# 4x4.net
KiCad netlist of a schematic drawn in EAGLE
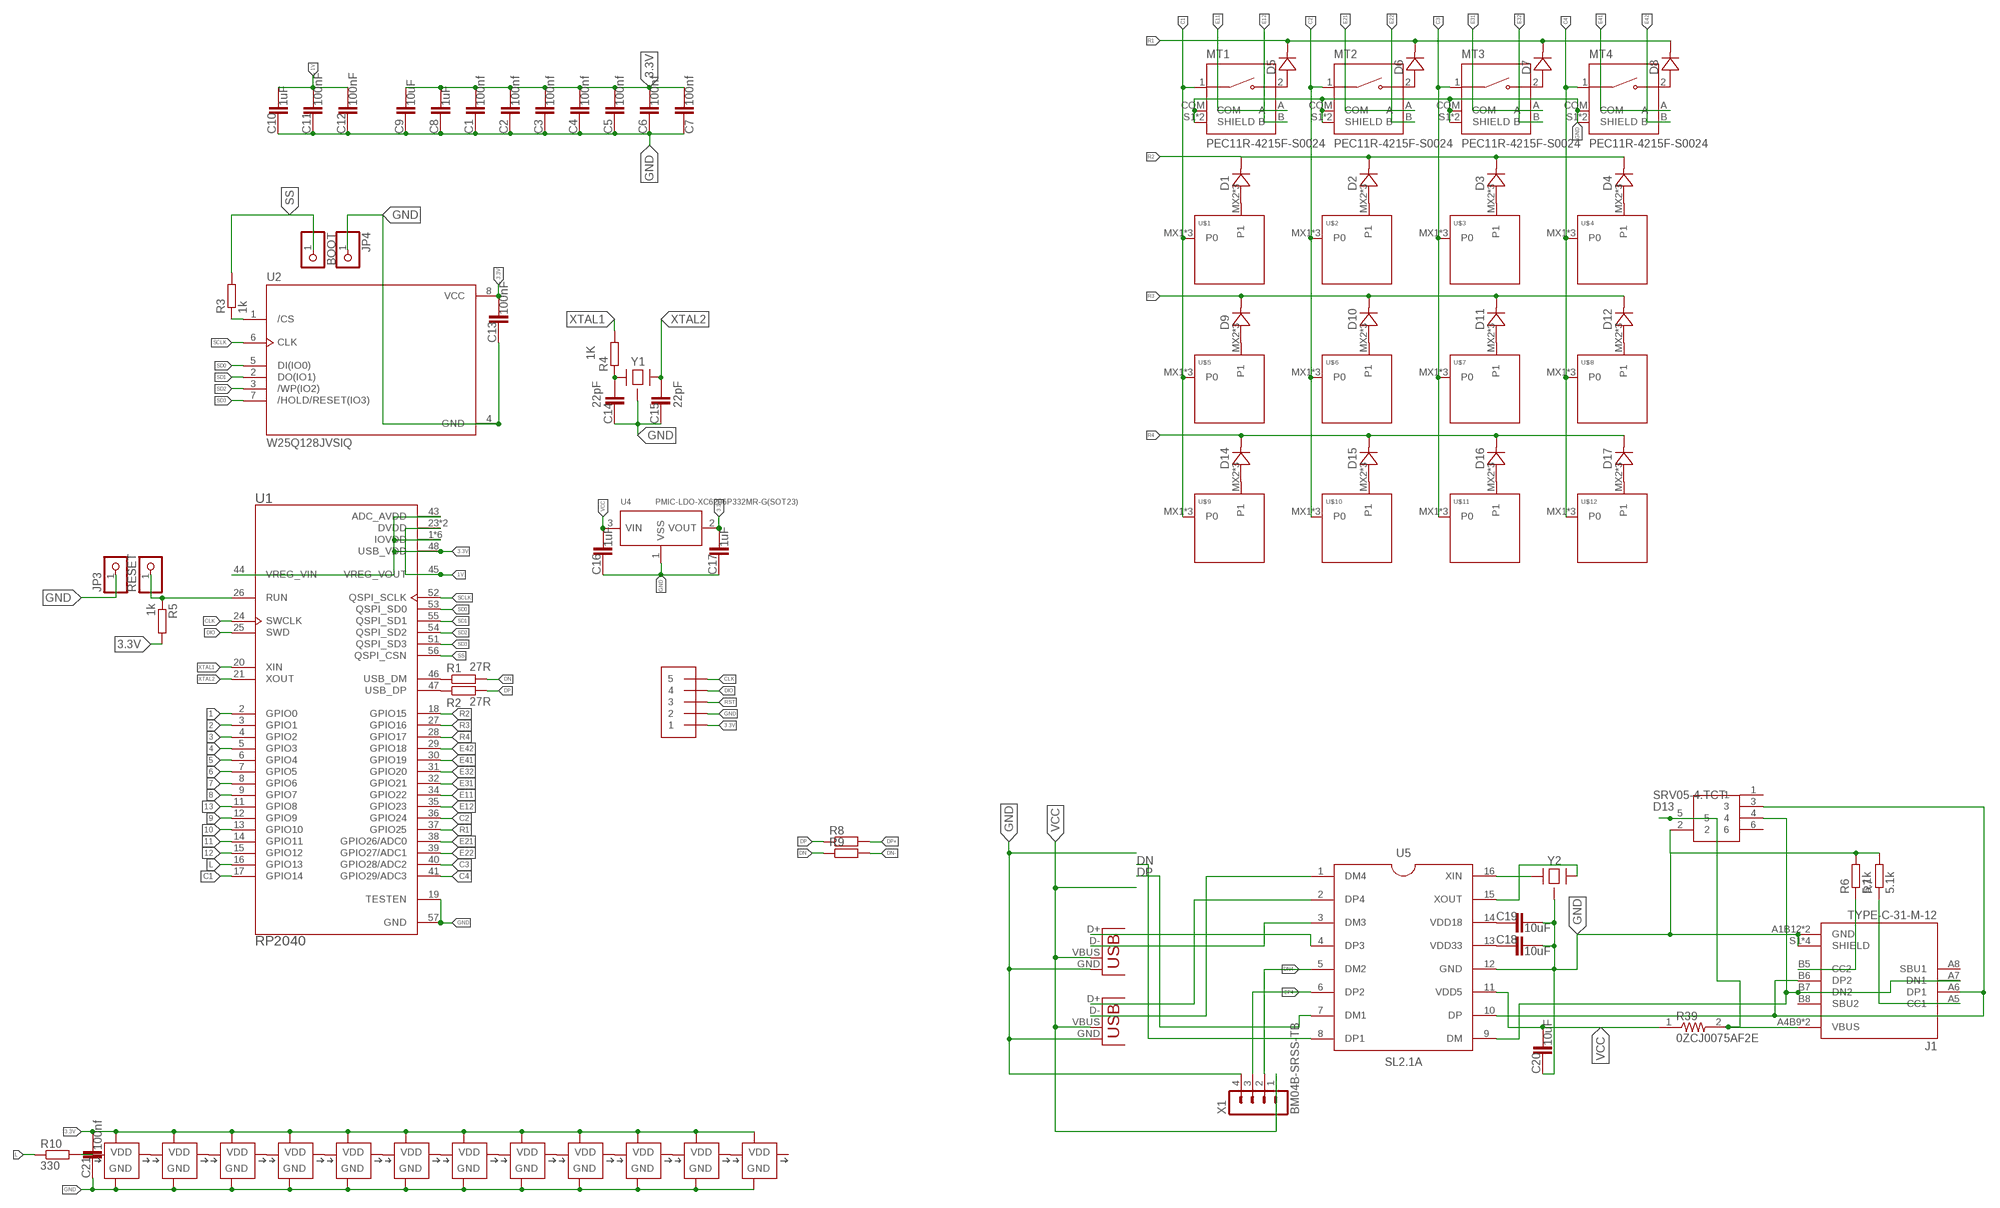
[diagram p0: schematic, sheet 1]

(export (version "E")
  (design (tool "Eeschema 10.0.6"))
  (components
    (comp (ref "BOOT")
      (value "PINHD-1X1")
      (footprint "eagle-import:1X01")
      (libsource (lib "eagle-import") (part "PINHD-1X1"))
    )
    (comp (ref "C1")
      (value "100nf")
      (footprint "eagle-import:C0603")
      (libsource (lib "eagle-import") (part "CAPACITOR-0603"))
    )
    (comp (ref "C2")
      (value "100nf")
      (footprint "eagle-import:C0603")
      (libsource (lib "eagle-import") (part "CAPACITOR-0603"))
    )
    (comp (ref "C3")
      (value "100nf")
      (footprint "eagle-import:C0603")
      (libsource (lib "eagle-import") (part "CAPACITOR-0603"))
    )
    (comp (ref "C4")
      (value "100nf")
      (footprint "eagle-import:C0603")
      (libsource (lib "eagle-import") (part "CAPACITOR-0603"))
    )
    (comp (ref "C5")
      (value "100nf")
      (footprint "eagle-import:C0603")
      (libsource (lib "eagle-import") (part "CAPACITOR-0603"))
    )
    (comp (ref "C6")
      (value "100nf")
      (footprint "eagle-import:C0603")
      (libsource (lib "eagle-import") (part "CAPACITOR-0603"))
    )
    (comp (ref "C7")
      (value "100nf")
      (footprint "eagle-import:C0603")
      (libsource (lib "eagle-import") (part "CAPACITOR-0603"))
    )
    (comp (ref "C8")
      (value "1uF")
      (footprint "eagle-import:C0603")
      (libsource (lib "eagle-import") (part "CAPACITOR-0603"))
    )
    (comp (ref "C9")
      (value "10uF")
      (footprint "eagle-import:C0603")
      (libsource (lib "eagle-import") (part "CAPACITOR-0603"))
    )
    (comp (ref "C10")
      (value "1uF")
      (footprint "eagle-import:C0603")
      (libsource (lib "eagle-import") (part "CAPACITOR-0603"))
    )
    (comp (ref "C11")
      (value "100nF")
      (footprint "eagle-import:C0603")
      (libsource (lib "eagle-import") (part "CAPACITOR-0603"))
    )
    (comp (ref "C12")
      (value "100nF")
      (footprint "eagle-import:C0603")
      (libsource (lib "eagle-import") (part "CAPACITOR-0603"))
    )
    (comp (ref "C13")
      (value "100nF")
      (footprint "eagle-import:C0603")
      (libsource (lib "eagle-import") (part "CAPACITOR-0603"))
    )
    (comp (ref "C14")
      (value "22pF")
      (footprint "eagle-import:C0603")
      (libsource (lib "eagle-import") (part "CAPACITOR-0603"))
    )
    (comp (ref "C15")
      (value "22pF")
      (footprint "eagle-import:C0603")
      (libsource (lib "eagle-import") (part "CAPACITOR-0603"))
    )
    (comp (ref "C16")
      (value "1uF")
      (footprint "eagle-import:C0603")
      (libsource (lib "eagle-import") (part "CAPACITOR-0603"))
    )
    (comp (ref "C17")
      (value "1uF")
      (footprint "eagle-import:C0603")
      (libsource (lib "eagle-import") (part "CAPACITOR-0603"))
    )
    (comp (ref "C18")
      (value "10uF")
      (footprint "eagle-import:C0603")
      (libsource (lib "eagle-import") (part "CAPACITOR-0603"))
    )
    (comp (ref "C19")
      (value "10uF")
      (footprint "eagle-import:C0603")
      (libsource (lib "eagle-import") (part "CAPACITOR-0603"))
    )
    (comp (ref "C20")
      (value "10uF")
      (footprint "eagle-import:C0603")
      (libsource (lib "eagle-import") (part "CAPACITOR-0603"))
    )
    (comp (ref "C21")
      (value "100nf")
      (footprint "eagle-import:C0603")
      (libsource (lib "eagle-import") (part "CAPACITOR-0603"))
    )
    (comp (ref "D1")
      (value "DIODE-SOD-123")
      (footprint "eagle-import:SOD-123")
      (libsource (lib "eagle-import") (part "DIODE-SOD-123"))
    )
    (comp (ref "D2")
      (value "DIODE-SOD-123")
      (footprint "eagle-import:SOD-123")
      (libsource (lib "eagle-import") (part "DIODE-SOD-123"))
    )
    (comp (ref "D3")
      (value "DIODE-SOD-123")
      (footprint "eagle-import:SOD-123")
      (libsource (lib "eagle-import") (part "DIODE-SOD-123"))
    )
    (comp (ref "D4")
      (value "DIODE-SOD-123")
      (footprint "eagle-import:SOD-123")
      (libsource (lib "eagle-import") (part "DIODE-SOD-123"))
    )
    (comp (ref "D5")
      (value "DIODE-SOD-123")
      (footprint "eagle-import:SOD-123")
      (libsource (lib "eagle-import") (part "DIODE-SOD-123"))
    )
    (comp (ref "D6")
      (value "DIODE-SOD-123")
      (footprint "eagle-import:SOD-123")
      (libsource (lib "eagle-import") (part "DIODE-SOD-123"))
    )
    (comp (ref "D7")
      (value "DIODE-SOD-123")
      (footprint "eagle-import:SOD-123")
      (libsource (lib "eagle-import") (part "DIODE-SOD-123"))
    )
    (comp (ref "D8")
      (value "DIODE-SOD-123")
      (footprint "eagle-import:SOD-123")
      (libsource (lib "eagle-import") (part "DIODE-SOD-123"))
    )
    (comp (ref "D9")
      (value "DIODE-SOD-123")
      (footprint "eagle-import:SOD-123")
      (libsource (lib "eagle-import") (part "DIODE-SOD-123"))
    )
    (comp (ref "D10")
      (value "DIODE-SOD-123")
      (footprint "eagle-import:SOD-123")
      (libsource (lib "eagle-import") (part "DIODE-SOD-123"))
    )
    (comp (ref "D11")
      (value "DIODE-SOD-123")
      (footprint "eagle-import:SOD-123")
      (libsource (lib "eagle-import") (part "DIODE-SOD-123"))
    )
    (comp (ref "D12")
      (value "DIODE-SOD-123")
      (footprint "eagle-import:SOD-123")
      (libsource (lib "eagle-import") (part "DIODE-SOD-123"))
    )
    (comp (ref "D13")
      (value "SRV05-4.TCT")
      (footprint "eagle-import:SOT95P280X145-6N")
      (fields (field (name "MF") "Semtech") (field (name "MP") "SRV05-4.TC"))
      (libsource (lib "eagle-import") (part "SRV05-4.TCT"))
    )
    (comp (ref "D14")
      (value "DIODE-SOD-123")
      (footprint "eagle-import:SOD-123")
      (libsource (lib "eagle-import") (part "DIODE-SOD-123"))
    )
    (comp (ref "D15")
      (value "DIODE-SOD-123")
      (footprint "eagle-import:SOD-123")
      (libsource (lib "eagle-import") (part "DIODE-SOD-123"))
    )
    (comp (ref "D16")
      (value "DIODE-SOD-123")
      (footprint "eagle-import:SOD-123")
      (libsource (lib "eagle-import") (part "DIODE-SOD-123"))
    )
    (comp (ref "D17")
      (value "DIODE-SOD-123")
      (footprint "eagle-import:SOD-123")
      (libsource (lib "eagle-import") (part "DIODE-SOD-123"))
    )
    (comp (ref "J1")
      (value "TYPE-C-31-M-12")
      (footprint "eagle-import:HRO_TYPE-C-31-M-12")
      (fields (field (name "MF") "HRO Electronics Co., Ltd."))
      (libsource (lib "eagle-import") (part "TYPE-C-31-M-12"))
    )
    (comp (ref "J2")
      (value "1X5")
      (footprint "eagle-import:1X05-3.5MM")
      (libsource (lib "eagle-import") (part "1X5"))
    )
    (comp (ref "JP3")
      (value "PINHD-1X1CB")
      (footprint "eagle-import:1X01-CLEANBIG")
      (libsource (lib "eagle-import") (part "PINHD-1X1CB"))
    )
    (comp (ref "JP4")
      (value "PINHD-1X1CB")
      (footprint "eagle-import:1X01-CLEANBIG")
      (libsource (lib "eagle-import") (part "PINHD-1X1CB"))
    )
    (comp (ref "MT1")
      (value "PEC11R-4215F-S0024")
      (footprint "eagle-import:XDCR_PEC11R-4215F-S0024")
      (fields (field (name "MF") "Bourns"))
      (libsource (lib "eagle-import") (part "PEC11R-4215F-S0024"))
    )
    (comp (ref "MT2")
      (value "PEC11R-4215F-S0024")
      (footprint "eagle-import:XDCR_PEC11R-4215F-S0024")
      (fields (field (name "MF") "Bourns"))
      (libsource (lib "eagle-import") (part "PEC11R-4215F-S0024"))
    )
    (comp (ref "MT3")
      (value "PEC11R-4215F-S0024")
      (footprint "eagle-import:XDCR_PEC11R-4215F-S0024")
      (fields (field (name "MF") "Bourns"))
      (libsource (lib "eagle-import") (part "PEC11R-4215F-S0024"))
    )
    (comp (ref "MT4")
      (value "PEC11R-4215F-S0024")
      (footprint "eagle-import:XDCR_PEC11R-4215F-S0024")
      (fields (field (name "MF") "Bourns"))
      (libsource (lib "eagle-import") (part "PEC11R-4215F-S0024"))
    )
    (comp (ref "R1")
      (value "27R")
      (footprint "eagle-import:R0603")
      (libsource (lib "eagle-import") (part "RESISTOR-0603"))
    )
    (comp (ref "R2")
      (value "27R")
      (footprint "eagle-import:R0603")
      (libsource (lib "eagle-import") (part "RESISTOR-0603"))
    )
    (comp (ref "R3")
      (value "1k")
      (footprint "eagle-import:R0603")
      (libsource (lib "eagle-import") (part "RESISTOR-0603"))
    )
    (comp (ref "R4")
      (value "1K")
      (footprint "eagle-import:R0603")
      (libsource (lib "eagle-import") (part "RESISTOR-0603"))
    )
    (comp (ref "R5")
      (value "1k")
      (footprint "eagle-import:R0603")
      (libsource (lib "eagle-import") (part "RESISTOR-0603"))
    )
    (comp (ref "R6")
      (value "5.1k")
      (footprint "eagle-import:R0603")
      (libsource (lib "eagle-import") (part "RESISTOR-0603"))
    )
    (comp (ref "R7")
      (value "5.1k")
      (footprint "eagle-import:R0603")
      (libsource (lib "eagle-import") (part "RESISTOR-0603"))
    )
    (comp (ref "R8")
      (value "RESISTOR-0405")
      (footprint "eagle-import:R0402")
      (libsource (lib "eagle-import") (part "RESISTOR-0405"))
    )
    (comp (ref "R9")
      (value "RESISTOR-0405")
      (footprint "eagle-import:R0402")
      (libsource (lib "eagle-import") (part "RESISTOR-0405"))
    )
    (comp (ref "R10")
      (value "330")
      (footprint "eagle-import:R0603")
      (libsource (lib "eagle-import") (part "RESISTOR-0603"))
    )
    (comp (ref "R39")
      (value "0ZCJ0075AF2E")
      (footprint "eagle-import:RESC3216X125N")
      (fields (field (name "MF") "Bel Fuse"))
      (libsource (lib "eagle-import") (part "0ZCJ0075AF2E"))
    )
    (comp (ref "RESET")
      (value "PINHD-1X1")
      (footprint "eagle-import:1X01")
      (libsource (lib "eagle-import") (part "PINHD-1X1"))
    )
    (comp (ref "U$1")
      (value "KEYSWITCH-PLAIN-MXHSPCB-1U")
      (footprint "eagle-import:MXHSPCB-1U")
      (libsource (lib "eagle-import") (part "KEYSWITCH-PLAIN-MXHSPCB-1U"))
    )
    (comp (ref "U$2")
      (value "KEYSWITCH-PLAIN-MXHSPCB-1U")
      (footprint "eagle-import:MXHSPCB-1U")
      (libsource (lib "eagle-import") (part "KEYSWITCH-PLAIN-MXHSPCB-1U"))
    )
    (comp (ref "U$3")
      (value "KEYSWITCH-PLAIN-MXHSPCB-1U")
      (footprint "eagle-import:MXHSPCB-1U")
      (libsource (lib "eagle-import") (part "KEYSWITCH-PLAIN-MXHSPCB-1U"))
    )
    (comp (ref "U$4")
      (value "KEYSWITCH-PLAIN-MXHSPCB-1U")
      (footprint "eagle-import:MXHSPCB-1U")
      (libsource (lib "eagle-import") (part "KEYSWITCH-PLAIN-MXHSPCB-1U"))
    )
    (comp (ref "U$5")
      (value "KEYSWITCH-PLAIN-MXHSPCB-1U")
      (footprint "eagle-import:MXHSPCB-1U")
      (libsource (lib "eagle-import") (part "KEYSWITCH-PLAIN-MXHSPCB-1U"))
    )
    (comp (ref "U$6")
      (value "KEYSWITCH-PLAIN-MXHSPCB-1U")
      (footprint "eagle-import:MXHSPCB-1U")
      (libsource (lib "eagle-import") (part "KEYSWITCH-PLAIN-MXHSPCB-1U"))
    )
    (comp (ref "U$7")
      (value "KEYSWITCH-PLAIN-MXHSPCB-1U")
      (footprint "eagle-import:MXHSPCB-1U")
      (libsource (lib "eagle-import") (part "KEYSWITCH-PLAIN-MXHSPCB-1U"))
    )
    (comp (ref "U$8")
      (value "KEYSWITCH-PLAIN-MXHSPCB-1U")
      (footprint "eagle-import:MXHSPCB-1U")
      (libsource (lib "eagle-import") (part "KEYSWITCH-PLAIN-MXHSPCB-1U"))
    )
    (comp (ref "U$9")
      (value "KEYSWITCH-PLAIN-MXHSPCB-1U")
      (footprint "eagle-import:MXHSPCB-1U")
      (libsource (lib "eagle-import") (part "KEYSWITCH-PLAIN-MXHSPCB-1U"))
    )
    (comp (ref "U$10")
      (value "KEYSWITCH-PLAIN-MXHSPCB-1U")
      (footprint "eagle-import:MXHSPCB-1U")
      (libsource (lib "eagle-import") (part "KEYSWITCH-PLAIN-MXHSPCB-1U"))
    )
    (comp (ref "U$11")
      (value "KEYSWITCH-PLAIN-MXHSPCB-1U")
      (footprint "eagle-import:MXHSPCB-1U")
      (libsource (lib "eagle-import") (part "KEYSWITCH-PLAIN-MXHSPCB-1U"))
    )
    (comp (ref "U$12")
      (value "KEYSWITCH-PLAIN-MXHSPCB-1U")
      (footprint "eagle-import:MXHSPCB-1U")
      (libsource (lib "eagle-import") (part "KEYSWITCH-PLAIN-MXHSPCB-1U"))
    )
    (comp (ref "U$13")
      (value "SK6812MINI")
      (footprint "eagle-import:LED-3535")
      (fields (field (name "MF") "DONGGUANG OPSCO OPTOELECTRONICS CO., LTD"))
      (libsource (lib "eagle-import") (part "SK6812MINI"))
    )
    (comp (ref "U$14")
      (value "SK6812MINI")
      (footprint "eagle-import:LED-3535")
      (fields (field (name "MF") "DONGGUANG OPSCO OPTOELECTRONICS CO., LTD"))
      (libsource (lib "eagle-import") (part "SK6812MINI"))
    )
    (comp (ref "U$15")
      (value "SK6812MINI")
      (footprint "eagle-import:LED-3535")
      (fields (field (name "MF") "DONGGUANG OPSCO OPTOELECTRONICS CO., LTD"))
      (libsource (lib "eagle-import") (part "SK6812MINI"))
    )
    (comp (ref "U$16")
      (value "SK6812MINI")
      (footprint "eagle-import:LED-3535")
      (fields (field (name "MF") "DONGGUANG OPSCO OPTOELECTRONICS CO., LTD"))
      (libsource (lib "eagle-import") (part "SK6812MINI"))
    )
    (comp (ref "U$17")
      (value "SK6812MINI")
      (footprint "eagle-import:LED-3535")
      (fields (field (name "MF") "DONGGUANG OPSCO OPTOELECTRONICS CO., LTD"))
      (libsource (lib "eagle-import") (part "SK6812MINI"))
    )
    (comp (ref "U$18")
      (value "SK6812MINI")
      (footprint "eagle-import:LED-3535")
      (fields (field (name "MF") "DONGGUANG OPSCO OPTOELECTRONICS CO., LTD"))
      (libsource (lib "eagle-import") (part "SK6812MINI"))
    )
    (comp (ref "U$19")
      (value "SK6812MINI")
      (footprint "eagle-import:LED-3535")
      (fields (field (name "MF") "DONGGUANG OPSCO OPTOELECTRONICS CO., LTD"))
      (libsource (lib "eagle-import") (part "SK6812MINI"))
    )
    (comp (ref "U$20")
      (value "SK6812MINI")
      (footprint "eagle-import:LED-3535")
      (fields (field (name "MF") "DONGGUANG OPSCO OPTOELECTRONICS CO., LTD"))
      (libsource (lib "eagle-import") (part "SK6812MINI"))
    )
    (comp (ref "U$21")
      (value "SK6812MINI")
      (footprint "eagle-import:LED-3535")
      (fields (field (name "MF") "DONGGUANG OPSCO OPTOELECTRONICS CO., LTD"))
      (libsource (lib "eagle-import") (part "SK6812MINI"))
    )
    (comp (ref "U$22")
      (value "SK6812MINI")
      (footprint "eagle-import:LED-3535")
      (fields (field (name "MF") "DONGGUANG OPSCO OPTOELECTRONICS CO., LTD"))
      (libsource (lib "eagle-import") (part "SK6812MINI"))
    )
    (comp (ref "U$23")
      (value "SK6812MINI")
      (footprint "eagle-import:LED-3535")
      (fields (field (name "MF") "DONGGUANG OPSCO OPTOELECTRONICS CO., LTD"))
      (libsource (lib "eagle-import") (part "SK6812MINI"))
    )
    (comp (ref "U$24")
      (value "SK6812MINI")
      (footprint "eagle-import:LED-3535")
      (fields (field (name "MF") "DONGGUANG OPSCO OPTOELECTRONICS CO., LTD"))
      (libsource (lib "eagle-import") (part "SK6812MINI"))
    )
    (comp (ref "U1")
      (value "RP2040")
      (footprint "eagle-import:QFN40P700X700X90-57N")
      (fields (field (name "MF") "Raspberry Pi"))
      (libsource (lib "eagle-import") (part "RP2040"))
    )
    (comp (ref "U2")
      (value "W25Q128JVSIQ")
      (footprint "eagle-import:SOIC127P790X216-8N")
      (fields (field (name "MF") "Winbond Electronics"))
      (libsource (lib "eagle-import") (part "W25Q128JVSIQ"))
    )
    (comp (ref "U4")
      (value "PMIC-LDO-XC6206P332MR-G(SOT23)")
      (footprint "eagle-import:SOT-23")
      (fields (field (name "MF") "Torex") (field (name "MP") "XC6206P332MR-G"))
      (libsource (lib "eagle-import") (part "PMIC-LDO-XC6206P332MR-G(SOT23)"))
    )
    (comp (ref "U5")
      (value "SL2.1A")
      (footprint "eagle-import:SO16")
      (fields (field (name "MF") "CoreChips ShenZhen CO.,Ltd"))
      (libsource (lib "eagle-import") (part "SL2.1A"))
    )
    (comp (ref "X1")
      (value "BM04B-SRSS-TB")
      (footprint "eagle-import:BM04B-SRSS-TB")
      (libsource (lib "eagle-import") (part "BM04B-SRSS-TB"))
    )
    (comp (ref "X4")
      (value "USB-A-H")
      (footprint "eagle-import:USB-A-H")
      (libsource (lib "eagle-import") (part "USB-A-H"))
    )
    (comp (ref "X5")
      (value "USB-A-H")
      (footprint "eagle-import:USB-A-H")
      (libsource (lib "eagle-import") (part "USB-A-H"))
    )
    (comp (ref "Y1")
      (value "CRYSTAL-4PIN-3.2X2.5")
      (footprint "eagle-import:CRYSTAL-3.2X2.5")
      (libsource (lib "eagle-import") (part "CRYSTAL-4PIN-3.2X2.5"))
    )
    (comp (ref "Y2")
      (value "CRYSTAL-4PIN-3.2X2.5")
      (footprint "eagle-import:CRYSTAL-3.2X2.5")
      (libsource (lib "eagle-import") (part "CRYSTAL-4PIN-3.2X2.5"))
    )
  )
  (nets
    (net (code "1") (name "1") (class "Default")
      (node (ref "U1") (pin "2") (pinfunction "GPIO0_2") (pintype "bidirectional"))
    )
    (net (code "2") (name "1V") (class "Default")
      (node (ref "C10") (pin "2") (pinfunction "2_2") (pintype "passive"))
      (node (ref "C11") (pin "2") (pinfunction "2_2") (pintype "passive"))
      (node (ref "C12") (pin "2") (pinfunction "2_2") (pintype "passive"))
      (node (ref "U1") (pin "23") (pinfunction "DVDD_23") (pintype "power_in"))
      (node (ref "U1") (pin "45") (pinfunction "VREG_VOUT_45") (pintype "output"))
      (node (ref "U1") (pin "50") (pinfunction "DVDD_50") (pintype "power_in"))
    )
    (net (code "3") (name "2") (class "Default")
      (node (ref "U1") (pin "3") (pinfunction "GPIO1_3") (pintype "bidirectional"))
    )
    (net (code "4") (name "3") (class "Default")
      (node (ref "U1") (pin "4") (pinfunction "GPIO2_4") (pintype "bidirectional"))
    )
    (net (code "5") (name "3.3V") (class "Default")
      (node (ref "C1") (pin "2") (pinfunction "2_2") (pintype "passive"))
      (node (ref "C13") (pin "2") (pinfunction "2_2") (pintype "passive"))
      (node (ref "C17") (pin "2") (pinfunction "2_2") (pintype "passive"))
      (node (ref "C2") (pin "2") (pinfunction "2_2") (pintype "passive"))
      (node (ref "C21") (pin "2") (pinfunction "2_2") (pintype "passive"))
      (node (ref "C3") (pin "2") (pinfunction "2_2") (pintype "passive"))
      (node (ref "C4") (pin "2") (pinfunction "2_2") (pintype "passive"))
      (node (ref "C5") (pin "2") (pinfunction "2_2") (pintype "passive"))
      (node (ref "C6") (pin "2") (pinfunction "2_2") (pintype "passive"))
      (node (ref "C7") (pin "2") (pinfunction "2_2") (pintype "passive"))
      (node (ref "C8") (pin "2") (pinfunction "2_2") (pintype "passive"))
      (node (ref "C9") (pin "2") (pinfunction "2_2") (pintype "passive"))
      (node (ref "J2") (pin "1") (pinfunction "1_1") (pintype "passive"))
      (node (ref "R5") (pin "2") (pinfunction "2_2") (pintype "passive"))
      (node (ref "U$13") (pin "4") (pinfunction "VDD_4") (pintype "power_in"))
      (node (ref "U$14") (pin "4") (pinfunction "VDD_4") (pintype "power_in"))
      (node (ref "U$15") (pin "4") (pinfunction "VDD_4") (pintype "power_in"))
      (node (ref "U$16") (pin "4") (pinfunction "VDD_4") (pintype "power_in"))
      (node (ref "U$17") (pin "4") (pinfunction "VDD_4") (pintype "power_in"))
      (node (ref "U$18") (pin "4") (pinfunction "VDD_4") (pintype "power_in"))
      (node (ref "U$19") (pin "4") (pinfunction "VDD_4") (pintype "power_in"))
      (node (ref "U$20") (pin "4") (pinfunction "VDD_4") (pintype "power_in"))
      (node (ref "U$21") (pin "4") (pinfunction "VDD_4") (pintype "power_in"))
      (node (ref "U$22") (pin "4") (pinfunction "VDD_4") (pintype "power_in"))
      (node (ref "U$23") (pin "4") (pinfunction "VDD_4") (pintype "power_in"))
      (node (ref "U$24") (pin "4") (pinfunction "VDD_4") (pintype "power_in"))
      (node (ref "U1") (pin "1") (pinfunction "IOVDD_1") (pintype "power_in"))
      (node (ref "U1") (pin "10") (pinfunction "IOVDD_10") (pintype "power_in"))
      (node (ref "U1") (pin "22") (pinfunction "IOVDD_22") (pintype "power_in"))
      (node (ref "U1") (pin "33") (pinfunction "IOVDD_33") (pintype "power_in"))
      (node (ref "U1") (pin "42") (pinfunction "IOVDD_42") (pintype "power_in"))
      (node (ref "U1") (pin "43") (pinfunction "ADC_AVDD_43") (pintype "power_in"))
      (node (ref "U1") (pin "44") (pinfunction "VREG_VIN_44") (pintype "input"))
      (node (ref "U1") (pin "48") (pinfunction "USB_VDD_48") (pintype "power_in"))
      (node (ref "U1") (pin "49") (pinfunction "IOVDD_49") (pintype "power_in"))
      (node (ref "U2") (pin "8") (pinfunction "VCC_8") (pintype "power_in"))
      (node (ref "U4") (pin "2") (pinfunction "VOUT_2") (pintype "output"))
    )
    (net (code "6") (name "4") (class "Default")
      (node (ref "U1") (pin "5") (pinfunction "GPIO3_5") (pintype "bidirectional"))
    )
    (net (code "7") (name "5") (class "Default")
      (node (ref "U1") (pin "6") (pinfunction "GPIO4_6") (pintype "bidirectional"))
    )
    (net (code "8") (name "6") (class "Default")
      (node (ref "U1") (pin "7") (pinfunction "GPIO5_7") (pintype "bidirectional"))
    )
    (net (code "9") (name "7") (class "Default")
      (node (ref "U1") (pin "8") (pinfunction "GPIO6_8") (pintype "bidirectional"))
    )
    (net (code "10") (name "8") (class "Default")
      (node (ref "U1") (pin "9") (pinfunction "GPIO7_9") (pintype "bidirectional"))
    )
    (net (code "11") (name "9") (class "Default")
      (node (ref "U1") (pin "12") (pinfunction "GPIO9_12") (pintype "bidirectional"))
    )
    (net (code "12") (name "10") (class "Default")
      (node (ref "U1") (pin "13") (pinfunction "GPIO10_13") (pintype "bidirectional"))
    )
    (net (code "13") (name "11") (class "Default")
      (node (ref "U1") (pin "14") (pinfunction "GPIO11_14") (pintype "bidirectional"))
    )
    (net (code "14") (name "12") (class "Default")
      (node (ref "U1") (pin "15") (pinfunction "GPIO12_15") (pintype "bidirectional"))
    )
    (net (code "15") (name "13") (class "Default")
      (node (ref "U1") (pin "11") (pinfunction "GPIO8_11") (pintype "bidirectional"))
    )
    (net (code "16") (name "C1") (class "Default")
      (node (ref "MT1") (pin "1") (pinfunction "1_1") (pintype "passive"))
      (node (ref "U$1") (pin "MX1") (pinfunction "P0_MX1") (pintype "bidirectional"))
      (node (ref "U$1") (pin "P$1") (pinfunction "P0_P$1") (pintype "bidirectional"))
      (node (ref "U$1") (pin "P$2") (pinfunction "P0_P$2") (pintype "bidirectional"))
      (node (ref "U$5") (pin "MX1") (pinfunction "P0_MX1") (pintype "bidirectional"))
      (node (ref "U$5") (pin "P$1") (pinfunction "P0_P$1") (pintype "bidirectional"))
      (node (ref "U$5") (pin "P$2") (pinfunction "P0_P$2") (pintype "bidirectional"))
      (node (ref "U$9") (pin "MX1") (pinfunction "P0_MX1") (pintype "bidirectional"))
      (node (ref "U$9") (pin "P$1") (pinfunction "P0_P$1") (pintype "bidirectional"))
      (node (ref "U$9") (pin "P$2") (pinfunction "P0_P$2") (pintype "bidirectional"))
      (node (ref "U1") (pin "17") (pinfunction "GPIO14_17") (pintype "bidirectional"))
    )
    (net (code "17") (name "C2") (class "Default")
      (node (ref "MT2") (pin "1") (pinfunction "1_1") (pintype "passive"))
      (node (ref "U$10") (pin "MX1") (pinfunction "P0_MX1") (pintype "bidirectional"))
      (node (ref "U$10") (pin "P$1") (pinfunction "P0_P$1") (pintype "bidirectional"))
      (node (ref "U$10") (pin "P$2") (pinfunction "P0_P$2") (pintype "bidirectional"))
      (node (ref "U$2") (pin "MX1") (pinfunction "P0_MX1") (pintype "bidirectional"))
      (node (ref "U$2") (pin "P$1") (pinfunction "P0_P$1") (pintype "bidirectional"))
      (node (ref "U$2") (pin "P$2") (pinfunction "P0_P$2") (pintype "bidirectional"))
      (node (ref "U$6") (pin "MX1") (pinfunction "P0_MX1") (pintype "bidirectional"))
      (node (ref "U$6") (pin "P$1") (pinfunction "P0_P$1") (pintype "bidirectional"))
      (node (ref "U$6") (pin "P$2") (pinfunction "P0_P$2") (pintype "bidirectional"))
      (node (ref "U1") (pin "36") (pinfunction "GPIO24_36") (pintype "bidirectional"))
    )
    (net (code "18") (name "C3") (class "Default")
      (node (ref "MT3") (pin "1") (pinfunction "1_1") (pintype "passive"))
      (node (ref "U$11") (pin "MX1") (pinfunction "P0_MX1") (pintype "bidirectional"))
      (node (ref "U$11") (pin "P$1") (pinfunction "P0_P$1") (pintype "bidirectional"))
      (node (ref "U$11") (pin "P$2") (pinfunction "P0_P$2") (pintype "bidirectional"))
      (node (ref "U$3") (pin "MX1") (pinfunction "P0_MX1") (pintype "bidirectional"))
      (node (ref "U$3") (pin "P$1") (pinfunction "P0_P$1") (pintype "bidirectional"))
      (node (ref "U$3") (pin "P$2") (pinfunction "P0_P$2") (pintype "bidirectional"))
      (node (ref "U$7") (pin "MX1") (pinfunction "P0_MX1") (pintype "bidirectional"))
      (node (ref "U$7") (pin "P$1") (pinfunction "P0_P$1") (pintype "bidirectional"))
      (node (ref "U$7") (pin "P$2") (pinfunction "P0_P$2") (pintype "bidirectional"))
      (node (ref "U1") (pin "40") (pinfunction "GPIO28/ADC2_40") (pintype "bidirectional"))
    )
    (net (code "19") (name "C4") (class "Default")
      (node (ref "MT4") (pin "1") (pinfunction "1_1") (pintype "passive"))
      (node (ref "U$12") (pin "MX1") (pinfunction "P0_MX1") (pintype "bidirectional"))
      (node (ref "U$12") (pin "P$1") (pinfunction "P0_P$1") (pintype "bidirectional"))
      (node (ref "U$12") (pin "P$2") (pinfunction "P0_P$2") (pintype "bidirectional"))
      (node (ref "U$4") (pin "MX1") (pinfunction "P0_MX1") (pintype "bidirectional"))
      (node (ref "U$4") (pin "P$1") (pinfunction "P0_P$1") (pintype "bidirectional"))
      (node (ref "U$4") (pin "P$2") (pinfunction "P0_P$2") (pintype "bidirectional"))
      (node (ref "U$8") (pin "MX1") (pinfunction "P0_MX1") (pintype "bidirectional"))
      (node (ref "U$8") (pin "P$1") (pinfunction "P0_P$1") (pintype "bidirectional"))
      (node (ref "U$8") (pin "P$2") (pinfunction "P0_P$2") (pintype "bidirectional"))
      (node (ref "U1") (pin "41") (pinfunction "GPIO29/ADC3_41") (pintype "bidirectional"))
    )
    (net (code "20") (name "CLK") (class "Default")
      (node (ref "J2") (pin "5") (pinfunction "5_5") (pintype "passive"))
      (node (ref "U1") (pin "24") (pinfunction "SWCLK_24") (pintype "input"))
    )
    (net (code "21") (name "DIO") (class "Default")
      (node (ref "J2") (pin "4") (pinfunction "4_4") (pintype "passive"))
      (node (ref "U1") (pin "25") (pinfunction "SWD_25") (pintype "bidirectional"))
    )
    (net (code "22") (name "DN") (class "Default")
      (node (ref "R1") (pin "2") (pinfunction "2_2") (pintype "passive"))
      (node (ref "R9") (pin "1") (pinfunction "1_1") (pintype "passive"))
      (node (ref "U5") (pin "8") (pinfunction "DP1_8") (pintype "bidirectional"))
    )
    (net (code "23") (name "DN-") (class "Default")
      (node (ref "D13") (pin "4") (pinfunction "4_4") (pintype "bidirectional"))
      (node (ref "J1") (pin "A7") (pinfunction "DN1_A7") (pintype "bidirectional"))
      (node (ref "J1") (pin "B7") (pinfunction "DN2_B7") (pintype "bidirectional"))
      (node (ref "R9") (pin "2") (pinfunction "2_2") (pintype "passive"))
      (node (ref "U5") (pin "9") (pinfunction "DM_9") (pintype "bidirectional"))
    )
    (net (code "24") (name "DN4") (class "Default")
      (node (ref "U5") (pin "5") (pinfunction "DM2_5") (pintype "bidirectional"))
      (node (ref "X1") (pin "2") (pinfunction "2_2") (pintype "passive"))
    )
    (net (code "25") (name "DP") (class "Default")
      (node (ref "R2") (pin "2") (pinfunction "2_2") (pintype "passive"))
      (node (ref "R8") (pin "1") (pinfunction "1_1") (pintype "passive"))
      (node (ref "U5") (pin "7") (pinfunction "DM1_7") (pintype "bidirectional"))
    )
    (net (code "26") (name "DP+") (class "Default")
      (node (ref "D13") (pin "3") (pinfunction "3_3") (pintype "bidirectional"))
      (node (ref "J1") (pin "A6") (pinfunction "DP1_A6") (pintype "bidirectional"))
      (node (ref "J1") (pin "B6") (pinfunction "DP2_B6") (pintype "bidirectional"))
      (node (ref "R8") (pin "2") (pinfunction "2_2") (pintype "passive"))
      (node (ref "U5") (pin "10") (pinfunction "DP_10") (pintype "bidirectional"))
    )
    (net (code "27") (name "DP4") (class "Default")
      (node (ref "U5") (pin "6") (pinfunction "DP2_6") (pintype "bidirectional"))
      (node (ref "X1") (pin "3") (pinfunction "3_3") (pintype "passive"))
    )
    (net (code "28") (name "E11") (class "Default")
      (node (ref "MT1") (pin "A") (pinfunction "A_A") (pintype "passive"))
      (node (ref "U1") (pin "34") (pinfunction "GPIO22_34") (pintype "bidirectional"))
    )
    (net (code "29") (name "E12") (class "Default")
      (node (ref "MT1") (pin "B") (pinfunction "B_B") (pintype "passive"))
      (node (ref "U1") (pin "35") (pinfunction "GPIO23_35") (pintype "bidirectional"))
    )
    (net (code "30") (name "E21") (class "Default")
      (node (ref "MT2") (pin "A") (pinfunction "A_A") (pintype "passive"))
      (node (ref "U1") (pin "38") (pinfunction "GPIO26/ADC0_38") (pintype "bidirectional"))
    )
    (net (code "31") (name "E22") (class "Default")
      (node (ref "MT2") (pin "B") (pinfunction "B_B") (pintype "passive"))
      (node (ref "U1") (pin "39") (pinfunction "GPIO27/ADC1_39") (pintype "bidirectional"))
    )
    (net (code "32") (name "E31") (class "Default")
      (node (ref "MT3") (pin "A") (pinfunction "A_A") (pintype "passive"))
      (node (ref "U1") (pin "32") (pinfunction "GPIO21_32") (pintype "bidirectional"))
    )
    (net (code "33") (name "E32") (class "Default")
      (node (ref "MT3") (pin "B") (pinfunction "B_B") (pintype "passive"))
      (node (ref "U1") (pin "31") (pinfunction "GPIO20_31") (pintype "bidirectional"))
    )
    (net (code "34") (name "E41") (class "Default")
      (node (ref "MT4") (pin "A") (pinfunction "A_A") (pintype "passive"))
      (node (ref "U1") (pin "30") (pinfunction "GPIO19_30") (pintype "bidirectional"))
    )
    (net (code "35") (name "E42") (class "Default")
      (node (ref "MT4") (pin "B") (pinfunction "B_B") (pintype "passive"))
      (node (ref "U1") (pin "29") (pinfunction "GPIO18_29") (pintype "bidirectional"))
    )
    (net (code "36") (name "GND") (class "Default")
      (node (ref "C1") (pin "1") (pinfunction "1_1") (pintype "passive"))
      (node (ref "C10") (pin "1") (pinfunction "1_1") (pintype "passive"))
      (node (ref "C11") (pin "1") (pinfunction "1_1") (pintype "passive"))
      (node (ref "C12") (pin "1") (pinfunction "1_1") (pintype "passive"))
      (node (ref "C13") (pin "1") (pinfunction "1_1") (pintype "passive"))
      (node (ref "C14") (pin "1") (pinfunction "1_1") (pintype "passive"))
      (node (ref "C15") (pin "1") (pinfunction "1_1") (pintype "passive"))
      (node (ref "C16") (pin "1") (pinfunction "1_1") (pintype "passive"))
      (node (ref "C17") (pin "1") (pinfunction "1_1") (pintype "passive"))
      (node (ref "C18") (pin "2") (pinfunction "2_2") (pintype "passive"))
      (node (ref "C19") (pin "2") (pinfunction "2_2") (pintype "passive"))
      (node (ref "C2") (pin "1") (pinfunction "1_1") (pintype "passive"))
      (node (ref "C20") (pin "1") (pinfunction "1_1") (pintype "passive"))
      (node (ref "C21") (pin "1") (pinfunction "1_1") (pintype "passive"))
      (node (ref "C3") (pin "1") (pinfunction "1_1") (pintype "passive"))
      (node (ref "C4") (pin "1") (pinfunction "1_1") (pintype "passive"))
      (node (ref "C5") (pin "1") (pinfunction "1_1") (pintype "passive"))
      (node (ref "C6") (pin "1") (pinfunction "1_1") (pintype "passive"))
      (node (ref "C7") (pin "1") (pinfunction "1_1") (pintype "passive"))
      (node (ref "C8") (pin "1") (pinfunction "1_1") (pintype "passive"))
      (node (ref "C9") (pin "1") (pinfunction "1_1") (pintype "passive"))
      (node (ref "D13") (pin "2") (pinfunction "2_2") (pintype "bidirectional"))
      (node (ref "J1") (pin "A1B12") (pinfunction "GND_A1B12") (pintype "power_in"))
      (node (ref "J1") (pin "B1A12") (pinfunction "GND_B1A12") (pintype "power_in"))
      (node (ref "J1") (pin "S1") (pinfunction "SHIELD_S1") (pintype "passive"))
      (node (ref "J1") (pin "S2") (pinfunction "SHIELD_S2") (pintype "passive"))
      (node (ref "J1") (pin "S3") (pinfunction "SHIELD_S3") (pintype "passive"))
      (node (ref "J1") (pin "S4") (pinfunction "SHIELD_S4") (pintype "passive"))
      (node (ref "J2") (pin "2") (pinfunction "2_2") (pintype "passive"))
      (node (ref "JP3") (pin "1") (pinfunction "1_1") (pintype "passive"))
      (node (ref "JP4") (pin "1") (pinfunction "1_1") (pintype "passive"))
      (node (ref "MT1") (pin "COM") (pinfunction "COM_COM") (pintype "passive"))
      (node (ref "MT1") (pin "S1") (pinfunction "SHIELD_S1") (pintype "passive"))
      (node (ref "MT1") (pin "S2") (pinfunction "SHIELD_S2") (pintype "passive"))
      (node (ref "MT2") (pin "COM") (pinfunction "COM_COM") (pintype "passive"))
      (node (ref "MT2") (pin "S1") (pinfunction "SHIELD_S1") (pintype "passive"))
      (node (ref "MT2") (pin "S2") (pinfunction "SHIELD_S2") (pintype "passive"))
      (node (ref "MT3") (pin "COM") (pinfunction "COM_COM") (pintype "passive"))
      (node (ref "MT3") (pin "S1") (pinfunction "SHIELD_S1") (pintype "passive"))
      (node (ref "MT3") (pin "S2") (pinfunction "SHIELD_S2") (pintype "passive"))
      (node (ref "MT4") (pin "COM") (pinfunction "COM_COM") (pintype "passive"))
      (node (ref "MT4") (pin "S1") (pinfunction "SHIELD_S1") (pintype "passive"))
      (node (ref "MT4") (pin "S2") (pinfunction "SHIELD_S2") (pintype "passive"))
      (node (ref "R6") (pin "2") (pinfunction "2_2") (pintype "passive"))
      (node (ref "R7") (pin "2") (pinfunction "2_2") (pintype "passive"))
      (node (ref "U$13") (pin "2") (pinfunction "GND_2") (pintype "power_in"))
      (node (ref "U$14") (pin "2") (pinfunction "GND_2") (pintype "power_in"))
      (node (ref "U$15") (pin "2") (pinfunction "GND_2") (pintype "power_in"))
      (node (ref "U$16") (pin "2") (pinfunction "GND_2") (pintype "power_in"))
      (node (ref "U$17") (pin "2") (pinfunction "GND_2") (pintype "power_in"))
      (node (ref "U$18") (pin "2") (pinfunction "GND_2") (pintype "power_in"))
      (node (ref "U$19") (pin "2") (pinfunction "GND_2") (pintype "power_in"))
      (node (ref "U$20") (pin "2") (pinfunction "GND_2") (pintype "power_in"))
      (node (ref "U$21") (pin "2") (pinfunction "GND_2") (pintype "power_in"))
      (node (ref "U$22") (pin "2") (pinfunction "GND_2") (pintype "power_in"))
      (node (ref "U$23") (pin "2") (pinfunction "GND_2") (pintype "power_in"))
      (node (ref "U$24") (pin "2") (pinfunction "GND_2") (pintype "power_in"))
      (node (ref "U1") (pin "19") (pinfunction "TESTEN_19") (pintype "passive"))
      (node (ref "U1") (pin "57") (pinfunction "GND_57") (pintype "power_in"))
      (node (ref "U2") (pin "4") (pinfunction "GND_4") (pintype "power_in"))
      (node (ref "U4") (pin "1") (pinfunction "VSS_1") (pintype "power_in"))
      (node (ref "U5") (pin "12") (pinfunction "GND_12") (pintype "bidirectional"))
      (node (ref "X1") (pin "4") (pinfunction "4_4") (pintype "passive"))
      (node (ref "X4") (pin "GND") (pinfunction "GND_GND") (pintype "bidirectional"))
      (node (ref "X5") (pin "GND") (pinfunction "GND_GND") (pintype "bidirectional"))
      (node (ref "Y1") (pin "2") (pinfunction "GND_2") (pintype "bidirectional"))
      (node (ref "Y1") (pin "4") (pinfunction "GND_4") (pintype "bidirectional"))
      (node (ref "Y2") (pin "2") (pinfunction "GND_2") (pintype "bidirectional"))
      (node (ref "Y2") (pin "4") (pinfunction "GND_4") (pintype "bidirectional"))
    )
    (net (code "37") (name "L") (class "Default")
      (node (ref "R10") (pin "1") (pinfunction "1_1") (pintype "passive"))
      (node (ref "U1") (pin "16") (pinfunction "GPIO13_16") (pintype "bidirectional"))
    )
    (net (code "38") (name "Net-(C14-Pad2)") (class "Default")
      (node (ref "C14") (pin "2") (pinfunction "2_2") (pintype "passive"))
      (node (ref "R4") (pin "1") (pinfunction "1_1") (pintype "passive"))
      (node (ref "Y1") (pin "1") (pinfunction "1_1") (pintype "passive"))
    )
    (net (code "39") (name "Net-(D1-PadA)") (class "Default")
      (node (ref "D1") (pin "A") (pinfunction "A_A") (pintype "passive"))
      (node (ref "U$1") (pin "MX2") (pinfunction "P1_MX2") (pintype "bidirectional"))
      (node (ref "U$1") (pin "P$3") (pinfunction "P1_P$3") (pintype "bidirectional"))
      (node (ref "U$1") (pin "P$4") (pinfunction "P1_P$4") (pintype "bidirectional"))
    )
    (net (code "40") (name "Net-(D2-PadA)") (class "Default")
      (node (ref "D2") (pin "A") (pinfunction "A_A") (pintype "passive"))
      (node (ref "U$2") (pin "MX2") (pinfunction "P1_MX2") (pintype "bidirectional"))
      (node (ref "U$2") (pin "P$3") (pinfunction "P1_P$3") (pintype "bidirectional"))
      (node (ref "U$2") (pin "P$4") (pinfunction "P1_P$4") (pintype "bidirectional"))
    )
    (net (code "41") (name "Net-(D3-PadA)") (class "Default")
      (node (ref "D3") (pin "A") (pinfunction "A_A") (pintype "passive"))
      (node (ref "U$3") (pin "MX2") (pinfunction "P1_MX2") (pintype "bidirectional"))
      (node (ref "U$3") (pin "P$3") (pinfunction "P1_P$3") (pintype "bidirectional"))
      (node (ref "U$3") (pin "P$4") (pinfunction "P1_P$4") (pintype "bidirectional"))
    )
    (net (code "42") (name "Net-(D4-PadA)") (class "Default")
      (node (ref "D4") (pin "A") (pinfunction "A_A") (pintype "passive"))
      (node (ref "U$4") (pin "MX2") (pinfunction "P1_MX2") (pintype "bidirectional"))
      (node (ref "U$4") (pin "P$3") (pinfunction "P1_P$3") (pintype "bidirectional"))
      (node (ref "U$4") (pin "P$4") (pinfunction "P1_P$4") (pintype "bidirectional"))
    )
    (net (code "43") (name "Net-(D5-PadA)") (class "Default")
      (node (ref "D5") (pin "A") (pinfunction "A_A") (pintype "passive"))
      (node (ref "MT1") (pin "2") (pinfunction "2_2") (pintype "passive"))
    )
    (net (code "44") (name "Net-(D6-PadA)") (class "Default")
      (node (ref "D6") (pin "A") (pinfunction "A_A") (pintype "passive"))
      (node (ref "MT2") (pin "2") (pinfunction "2_2") (pintype "passive"))
    )
    (net (code "45") (name "Net-(D7-PadA)") (class "Default")
      (node (ref "D7") (pin "A") (pinfunction "A_A") (pintype "passive"))
      (node (ref "MT3") (pin "2") (pinfunction "2_2") (pintype "passive"))
    )
    (net (code "46") (name "Net-(D8-PadA)") (class "Default")
      (node (ref "D8") (pin "A") (pinfunction "A_A") (pintype "passive"))
      (node (ref "MT4") (pin "2") (pinfunction "2_2") (pintype "passive"))
    )
    (net (code "47") (name "Net-(D9-PadA)") (class "Default")
      (node (ref "D9") (pin "A") (pinfunction "A_A") (pintype "passive"))
      (node (ref "U$5") (pin "MX2") (pinfunction "P1_MX2") (pintype "bidirectional"))
      (node (ref "U$5") (pin "P$3") (pinfunction "P1_P$3") (pintype "bidirectional"))
      (node (ref "U$5") (pin "P$4") (pinfunction "P1_P$4") (pintype "bidirectional"))
    )
    (net (code "48") (name "Net-(D10-PadA)") (class "Default")
      (node (ref "D10") (pin "A") (pinfunction "A_A") (pintype "passive"))
      (node (ref "U$6") (pin "MX2") (pinfunction "P1_MX2") (pintype "bidirectional"))
      (node (ref "U$6") (pin "P$3") (pinfunction "P1_P$3") (pintype "bidirectional"))
      (node (ref "U$6") (pin "P$4") (pinfunction "P1_P$4") (pintype "bidirectional"))
    )
    (net (code "49") (name "Net-(D11-PadA)") (class "Default")
      (node (ref "D11") (pin "A") (pinfunction "A_A") (pintype "passive"))
      (node (ref "U$7") (pin "MX2") (pinfunction "P1_MX2") (pintype "bidirectional"))
      (node (ref "U$7") (pin "P$3") (pinfunction "P1_P$3") (pintype "bidirectional"))
      (node (ref "U$7") (pin "P$4") (pinfunction "P1_P$4") (pintype "bidirectional"))
    )
    (net (code "50") (name "Net-(D12-PadA)") (class "Default")
      (node (ref "D12") (pin "A") (pinfunction "A_A") (pintype "passive"))
      (node (ref "U$8") (pin "MX2") (pinfunction "P1_MX2") (pintype "bidirectional"))
      (node (ref "U$8") (pin "P$3") (pinfunction "P1_P$3") (pintype "bidirectional"))
      (node (ref "U$8") (pin "P$4") (pinfunction "P1_P$4") (pintype "bidirectional"))
    )
    (net (code "51") (name "Net-(D13-Pad5)") (class "Default")
      (node (ref "D13") (pin "5") (pinfunction "5_5") (pintype "bidirectional"))
      (node (ref "J1") (pin "A4B9") (pinfunction "VBUS_A4B9") (pintype "power_in"))
      (node (ref "J1") (pin "B4A9") (pinfunction "VBUS_B4A9") (pintype "power_in"))
      (node (ref "R39") (pin "2") (pinfunction "2_2") (pintype "passive"))
    )
    (net (code "52") (name "Net-(D14-PadA)") (class "Default")
      (node (ref "D14") (pin "A") (pinfunction "A_A") (pintype "passive"))
      (node (ref "U$9") (pin "MX2") (pinfunction "P1_MX2") (pintype "bidirectional"))
      (node (ref "U$9") (pin "P$3") (pinfunction "P1_P$3") (pintype "bidirectional"))
      (node (ref "U$9") (pin "P$4") (pinfunction "P1_P$4") (pintype "bidirectional"))
    )
    (net (code "53") (name "Net-(D15-PadA)") (class "Default")
      (node (ref "D15") (pin "A") (pinfunction "A_A") (pintype "passive"))
      (node (ref "U$10") (pin "MX2") (pinfunction "P1_MX2") (pintype "bidirectional"))
      (node (ref "U$10") (pin "P$3") (pinfunction "P1_P$3") (pintype "bidirectional"))
      (node (ref "U$10") (pin "P$4") (pinfunction "P1_P$4") (pintype "bidirectional"))
    )
    (net (code "54") (name "Net-(D16-PadA)") (class "Default")
      (node (ref "D16") (pin "A") (pinfunction "A_A") (pintype "passive"))
      (node (ref "U$11") (pin "MX2") (pinfunction "P1_MX2") (pintype "bidirectional"))
      (node (ref "U$11") (pin "P$3") (pinfunction "P1_P$3") (pintype "bidirectional"))
      (node (ref "U$11") (pin "P$4") (pinfunction "P1_P$4") (pintype "bidirectional"))
    )
    (net (code "55") (name "Net-(D17-PadA)") (class "Default")
      (node (ref "D17") (pin "A") (pinfunction "A_A") (pintype "passive"))
      (node (ref "U$12") (pin "MX2") (pinfunction "P1_MX2") (pintype "bidirectional"))
      (node (ref "U$12") (pin "P$3") (pinfunction "P1_P$3") (pintype "bidirectional"))
      (node (ref "U$12") (pin "P$4") (pinfunction "P1_P$4") (pintype "bidirectional"))
    )
    (net (code "56") (name "Net-(J1-CC1)") (class "Default")
      (node (ref "J1") (pin "A5") (pinfunction "CC1_A5") (pintype "bidirectional"))
      (node (ref "R7") (pin "1") (pinfunction "1_1") (pintype "passive"))
    )
    (net (code "57") (name "Net-(J1-CC2)") (class "Default")
      (node (ref "J1") (pin "B5") (pinfunction "CC2_B5") (pintype "bidirectional"))
      (node (ref "R6") (pin "1") (pinfunction "1_1") (pintype "passive"))
    )
    (net (code "58") (name "Net-(U$13-DI)") (class "Default")
      (node (ref "U$13") (pin "1") (pinfunction "DI_1") (pintype "input"))
      (node (ref "U$19") (pin "3") (pinfunction "DO_3") (pintype "output"))
    )
    (net (code "59") (name "Net-(U$13-DO)") (class "Default")
      (node (ref "U$13") (pin "3") (pinfunction "DO_3") (pintype "output"))
      (node (ref "U$14") (pin "1") (pinfunction "DI_1") (pintype "input"))
    )
    (net (code "60") (name "Net-(U$14-DO)") (class "Default")
      (node (ref "U$14") (pin "3") (pinfunction "DO_3") (pintype "output"))
      (node (ref "U$15") (pin "1") (pinfunction "DI_1") (pintype "input"))
    )
    (net (code "61") (name "Net-(U$15-DO)") (class "Default")
      (node (ref "U$15") (pin "3") (pinfunction "DO_3") (pintype "output"))
      (node (ref "U$16") (pin "1") (pinfunction "DI_1") (pintype "input"))
    )
    (net (code "62") (name "Net-(U$16-DO)") (class "Default")
      (node (ref "U$16") (pin "3") (pinfunction "DO_3") (pintype "output"))
      (node (ref "U$20") (pin "1") (pinfunction "DI_1") (pintype "input"))
    )
    (net (code "63") (name "Net-(U$17-DI)") (class "Default")
      (node (ref "R10") (pin "2") (pinfunction "2_2") (pintype "passive"))
      (node (ref "U$17") (pin "1") (pinfunction "DI_1") (pintype "input"))
    )
    (net (code "64") (name "Net-(U$17-DO)") (class "Default")
      (node (ref "U$17") (pin "3") (pinfunction "DO_3") (pintype "output"))
      (node (ref "U$18") (pin "1") (pinfunction "DI_1") (pintype "input"))
    )
    (net (code "65") (name "Net-(U$18-DO)") (class "Default")
      (node (ref "U$18") (pin "3") (pinfunction "DO_3") (pintype "output"))
      (node (ref "U$19") (pin "1") (pinfunction "DI_1") (pintype "input"))
    )
    (net (code "66") (name "Net-(U$20-DO)") (class "Default")
      (node (ref "U$20") (pin "3") (pinfunction "DO_3") (pintype "output"))
      (node (ref "U$21") (pin "1") (pinfunction "DI_1") (pintype "input"))
    )
    (net (code "67") (name "Net-(U$21-DO)") (class "Default")
      (node (ref "U$21") (pin "3") (pinfunction "DO_3") (pintype "output"))
      (node (ref "U$22") (pin "1") (pinfunction "DI_1") (pintype "input"))
    )
    (net (code "68") (name "Net-(U$22-DO)") (class "Default")
      (node (ref "U$22") (pin "3") (pinfunction "DO_3") (pintype "output"))
      (node (ref "U$23") (pin "1") (pinfunction "DI_1") (pintype "input"))
    )
    (net (code "69") (name "Net-(U$23-DO)") (class "Default")
      (node (ref "U$23") (pin "3") (pinfunction "DO_3") (pintype "output"))
      (node (ref "U$24") (pin "1") (pinfunction "DI_1") (pintype "input"))
    )
    (net (code "70") (name "Net-(U1-USB_DM)") (class "Default")
      (node (ref "R1") (pin "1") (pinfunction "1_1") (pintype "passive"))
      (node (ref "U1") (pin "46") (pinfunction "USB_DM_46") (pintype "bidirectional"))
    )
    (net (code "71") (name "Net-(U1-USB_DP)") (class "Default")
      (node (ref "R2") (pin "1") (pinfunction "1_1") (pintype "passive"))
      (node (ref "U1") (pin "47") (pinfunction "USB_DP_47") (pintype "bidirectional"))
    )
    (net (code "72") (name "Net-(U2-{slash}CS)") (class "Default")
      (node (ref "R3") (pin "1") (pinfunction "1_1") (pintype "passive"))
      (node (ref "U2") (pin "1") (pinfunction "/CS_1") (pintype "input"))
    )
    (net (code "73") (name "Net-(U5-DM3)") (class "Default")
      (node (ref "U5") (pin "3") (pinfunction "DM3_3") (pintype "bidirectional"))
      (node (ref "X4") (pin "D-") (pinfunction "D-_D-") (pintype "bidirectional"))
    )
    (net (code "74") (name "Net-(U5-DM4)") (class "Default")
      (node (ref "U5") (pin "1") (pinfunction "DM4_1") (pintype "bidirectional"))
      (node (ref "X5") (pin "D-") (pinfunction "D-_D-") (pintype "bidirectional"))
    )
    (net (code "75") (name "Net-(U5-DP3)") (class "Default")
      (node (ref "U5") (pin "4") (pinfunction "DP3_4") (pintype "bidirectional"))
      (node (ref "X4") (pin "D+") (pinfunction "D+_D+") (pintype "bidirectional"))
    )
    (net (code "76") (name "Net-(U5-DP4)") (class "Default")
      (node (ref "U5") (pin "2") (pinfunction "DP4_2") (pintype "bidirectional"))
      (node (ref "X5") (pin "D+") (pinfunction "D+_D+") (pintype "bidirectional"))
    )
    (net (code "77") (name "Net-(U5-VDD18)") (class "Default")
      (node (ref "C19") (pin "1") (pinfunction "1_1") (pintype "passive"))
      (node (ref "U5") (pin "14") (pinfunction "VDD18_14") (pintype "bidirectional"))
    )
    (net (code "78") (name "Net-(U5-VDD33)") (class "Default")
      (node (ref "C18") (pin "1") (pinfunction "1_1") (pintype "passive"))
      (node (ref "U5") (pin "13") (pinfunction "VDD33_13") (pintype "bidirectional"))
    )
    (net (code "79") (name "Net-(U5-XIN)") (class "Default")
      (node (ref "U5") (pin "16") (pinfunction "XIN_16") (pintype "bidirectional"))
      (node (ref "Y2") (pin "1") (pinfunction "1_1") (pintype "passive"))
    )
    (net (code "80") (name "Net-(U5-XOUT)") (class "Default")
      (node (ref "U5") (pin "15") (pinfunction "XOUT_15") (pintype "bidirectional"))
      (node (ref "Y2") (pin "3") (pinfunction "2_3") (pintype "passive"))
    )
    (net (code "81") (name "R1") (class "Default")
      (node (ref "D5") (pin "C") (pinfunction "C_C") (pintype "passive"))
      (node (ref "D6") (pin "C") (pinfunction "C_C") (pintype "passive"))
      (node (ref "D7") (pin "C") (pinfunction "C_C") (pintype "passive"))
      (node (ref "D8") (pin "C") (pinfunction "C_C") (pintype "passive"))
      (node (ref "U1") (pin "37") (pinfunction "GPIO25_37") (pintype "bidirectional"))
    )
    (net (code "82") (name "R2") (class "Default")
      (node (ref "D1") (pin "C") (pinfunction "C_C") (pintype "passive"))
      (node (ref "D2") (pin "C") (pinfunction "C_C") (pintype "passive"))
      (node (ref "D3") (pin "C") (pinfunction "C_C") (pintype "passive"))
      (node (ref "D4") (pin "C") (pinfunction "C_C") (pintype "passive"))
      (node (ref "U1") (pin "18") (pinfunction "GPIO15_18") (pintype "bidirectional"))
    )
    (net (code "83") (name "R3") (class "Default")
      (node (ref "D10") (pin "C") (pinfunction "C_C") (pintype "passive"))
      (node (ref "D11") (pin "C") (pinfunction "C_C") (pintype "passive"))
      (node (ref "D12") (pin "C") (pinfunction "C_C") (pintype "passive"))
      (node (ref "D9") (pin "C") (pinfunction "C_C") (pintype "passive"))
      (node (ref "U1") (pin "27") (pinfunction "GPIO16_27") (pintype "bidirectional"))
    )
    (net (code "84") (name "R4") (class "Default")
      (node (ref "D14") (pin "C") (pinfunction "C_C") (pintype "passive"))
      (node (ref "D15") (pin "C") (pinfunction "C_C") (pintype "passive"))
      (node (ref "D16") (pin "C") (pinfunction "C_C") (pintype "passive"))
      (node (ref "D17") (pin "C") (pinfunction "C_C") (pintype "passive"))
      (node (ref "U1") (pin "28") (pinfunction "GPIO17_28") (pintype "bidirectional"))
    )
    (net (code "85") (name "RST") (class "Default")
      (node (ref "J2") (pin "3") (pinfunction "3_3") (pintype "passive"))
      (node (ref "R5") (pin "1") (pinfunction "1_1") (pintype "passive"))
      (node (ref "RESET") (pin "1") (pinfunction "1_1") (pintype "passive"))
      (node (ref "U1") (pin "26") (pinfunction "RUN_26") (pintype "input"))
    )
    (net (code "86") (name "SCLK") (class "Default")
      (node (ref "U1") (pin "52") (pinfunction "QSPI_SCLK_52") (pintype "bidirectional"))
      (node (ref "U2") (pin "6") (pinfunction "CLK_6") (pintype "input"))
    )
    (net (code "87") (name "SD0") (class "Default")
      (node (ref "U1") (pin "53") (pinfunction "QSPI_SD0_53") (pintype "bidirectional"))
      (node (ref "U2") (pin "5") (pinfunction "DI(IO0)_5") (pintype "bidirectional"))
    )
    (net (code "88") (name "SD1") (class "Default")
      (node (ref "U1") (pin "55") (pinfunction "QSPI_SD1_55") (pintype "bidirectional"))
      (node (ref "U2") (pin "2") (pinfunction "DO(IO1)_2") (pintype "bidirectional"))
    )
    (net (code "89") (name "SD2") (class "Default")
      (node (ref "U1") (pin "54") (pinfunction "QSPI_SD2_54") (pintype "bidirectional"))
      (node (ref "U2") (pin "3") (pinfunction "/WP(IO2)_3") (pintype "bidirectional"))
    )
    (net (code "90") (name "SD3") (class "Default")
      (node (ref "U1") (pin "51") (pinfunction "QSPI_SD3_51") (pintype "bidirectional"))
      (node (ref "U2") (pin "7") (pinfunction "/HOLD/RESET(IO3)_7") (pintype "bidirectional"))
    )
    (net (code "91") (name "SS") (class "Default")
      (node (ref "BOOT") (pin "1") (pinfunction "1_1") (pintype "passive"))
      (node (ref "R3") (pin "2") (pinfunction "2_2") (pintype "passive"))
      (node (ref "U1") (pin "56") (pinfunction "QSPI_CSN_56") (pintype "bidirectional"))
    )
    (net (code "92") (name "VCC") (class "Default")
      (node (ref "C16") (pin "2") (pinfunction "2_2") (pintype "passive"))
      (node (ref "C20") (pin "2") (pinfunction "2_2") (pintype "passive"))
      (node (ref "R39") (pin "1") (pinfunction "1_1") (pintype "passive"))
      (node (ref "U4") (pin "3") (pinfunction "VIN_3") (pintype "input"))
      (node (ref "U5") (pin "11") (pinfunction "VDD5_11") (pintype "bidirectional"))
      (node (ref "X1") (pin "1") (pinfunction "1_1") (pintype "passive"))
      (node (ref "X4") (pin "VBUS") (pinfunction "VBUS_VBUS") (pintype "bidirectional"))
      (node (ref "X5") (pin "VBUS") (pinfunction "VBUS_VBUS") (pintype "bidirectional"))
    )
    (net (code "93") (name "XTAL1") (class "Default")
      (node (ref "R4") (pin "2") (pinfunction "2_2") (pintype "passive"))
      (node (ref "U1") (pin "20") (pinfunction "XIN_20") (pintype "input"))
    )
    (net (code "94") (name "XTAL2") (class "Default")
      (node (ref "C15") (pin "2") (pinfunction "2_2") (pintype "passive"))
      (node (ref "U1") (pin "21") (pinfunction "XOUT_21") (pintype "output"))
      (node (ref "Y1") (pin "3") (pinfunction "2_3") (pintype "passive"))
    )
    (net (code "95") (name "unconnected-(D13-Pad1)") (class "Default")
      (node (ref "D13") (pin "1") (pinfunction "1_1") (pintype "bidirectional"))
    )
    (net (code "96") (name "unconnected-(D13-Pad6)") (class "Default")
      (node (ref "D13") (pin "6") (pinfunction "6_6") (pintype "bidirectional"))
    )
    (net (code "97") (name "unconnected-(J1-SBU1-PadA8)") (class "Default")
      (node (ref "J1") (pin "A8") (pinfunction "SBU1_A8") (pintype "bidirectional"))
    )
    (net (code "98") (name "unconnected-(J1-SBU2-PadB8)") (class "Default")
      (node (ref "J1") (pin "B8") (pinfunction "SBU2_B8") (pintype "bidirectional"))
    )
    (net (code "99") (name "unconnected-(U$24-DO-Pad3)") (class "Default")
      (node (ref "U$24") (pin "3") (pinfunction "DO_3") (pintype "output"))
    )
  )
)
